# ENGR12L_Security_Alarm_v2.net
KiCad netlist of a schematic drawn in EAGLE
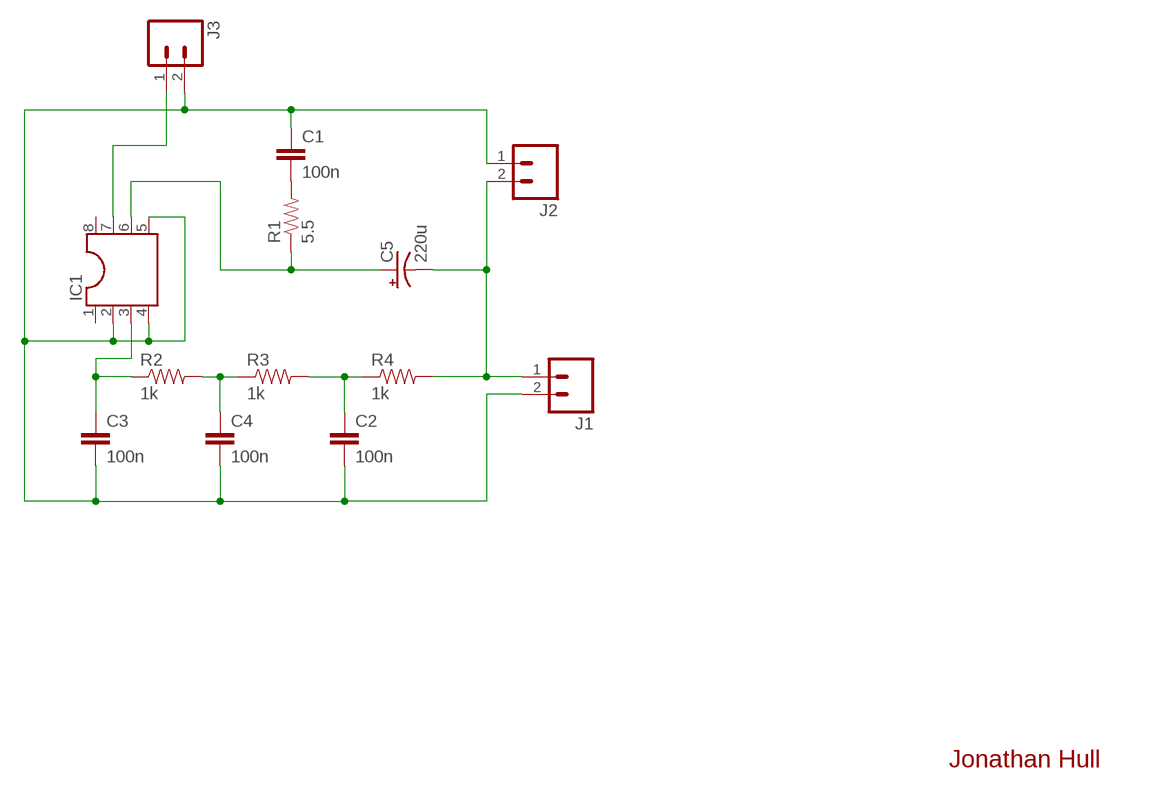
[diagram p0: schematic, sheet 1]

(export (version "E")
  (design (tool "Eeschema 10.0.6"))
  (components
    (comp (ref "C1")
      (value "100n")
      (footprint "eagle-import:CAP-PTH-SMALL")
      (libsource (lib "eagle-import") (part "CAPPTH"))
    )
    (comp (ref "C2")
      (value "100n")
      (footprint "eagle-import:CAP-PTH-SMALL")
      (libsource (lib "eagle-import") (part "CAPPTH"))
    )
    (comp (ref "C3")
      (value "100n")
      (footprint "eagle-import:CAP-PTH-SMALL")
      (libsource (lib "eagle-import") (part "CAPPTH"))
    )
    (comp (ref "C4")
      (value "100n")
      (footprint "eagle-import:CAP-PTH-SMALL")
      (libsource (lib "eagle-import") (part "CAPPTH"))
    )
    (comp (ref "C5")
      (value "220u")
      (footprint "eagle-import:CPOL-RADIAL-10UF-25V")
      (libsource (lib "eagle-import") (part "CAP_POLPTH2"))
    )
    (comp (ref "IC1")
      (value "DIL8S")
      (footprint "eagle-import:SOCKET-08")
      (libsource (lib "eagle-import") (part "DIL8S"))
    )
    (comp (ref "J1")
      (value "M023.5MM")
      (footprint "eagle-import:SCREWTERMINAL-3.5MM-2")
      (libsource (lib "eagle-import") (part "M023.5MM"))
    )
    (comp (ref "J2")
      (value "M023.5MM")
      (footprint "eagle-import:SCREWTERMINAL-3.5MM-2")
      (libsource (lib "eagle-import") (part "M023.5MM"))
    )
    (comp (ref "J3")
      (value "M023.5MM")
      (footprint "eagle-import:SCREWTERMINAL-3.5MM-2")
      (libsource (lib "eagle-import") (part "M023.5MM"))
    )
    (comp (ref "R1")
      (value "5.5")
      (footprint "eagle-import:AXIAL-0.4")
      (libsource (lib "eagle-import") (part "RESISTORPTH-1/4W"))
    )
    (comp (ref "R2")
      (value "1k")
      (footprint "eagle-import:AXIAL-0.4")
      (libsource (lib "eagle-import") (part "RESISTORPTH-1/4W"))
    )
    (comp (ref "R3")
      (value "1k")
      (footprint "eagle-import:AXIAL-0.4")
      (libsource (lib "eagle-import") (part "RESISTORPTH-1/4W"))
    )
    (comp (ref "R4")
      (value "1k")
      (footprint "eagle-import:AXIAL-0.4")
      (libsource (lib "eagle-import") (part "RESISTORPTH-1/4W"))
    )
  )
  (nets
    (net (code "1") (name "Net-(C1-Pad1)") (class "Default")
      (node (ref "C1") (pin "1") (pinfunction "1_1") (pintype "passive"))
      (node (ref "C2") (pin "2") (pinfunction "2_2") (pintype "passive"))
      (node (ref "C3") (pin "2") (pinfunction "2_2") (pintype "passive"))
      (node (ref "C4") (pin "2") (pinfunction "2_2") (pintype "passive"))
      (node (ref "IC1") (pin "2") (pinfunction "2_2") (pintype "passive"))
      (node (ref "IC1") (pin "4") (pinfunction "4_4") (pintype "passive"))
      (node (ref "IC1") (pin "5") (pinfunction "5_5") (pintype "passive"))
      (node (ref "J1") (pin "2") (pinfunction "2_2") (pintype "passive"))
      (node (ref "J2") (pin "1") (pinfunction "1_1") (pintype "passive"))
      (node (ref "J3") (pin "2") (pinfunction "2_2") (pintype "passive"))
    )
    (net (code "2") (name "Net-(C5-+)") (class "Default")
      (node (ref "C5") (pin "1") (pinfunction "+_1") (pintype "passive"))
      (node (ref "IC1") (pin "6") (pinfunction "6_6") (pintype "passive"))
      (node (ref "R1") (pin "P$1") (pinfunction "1_P$1") (pintype "passive"))
    )
    (net (code "3") (name "Net-(C5--)") (class "Default")
      (node (ref "C5") (pin "2") (pinfunction "-_2") (pintype "passive"))
      (node (ref "J1") (pin "1") (pinfunction "1_1") (pintype "passive"))
      (node (ref "J2") (pin "2") (pinfunction "2_2") (pintype "passive"))
      (node (ref "R4") (pin "P$2") (pinfunction "2_P$2") (pintype "passive"))
    )
    (net (code "4") (name "Net-(IC1-Pad7)") (class "Default")
      (node (ref "IC1") (pin "7") (pinfunction "7_7") (pintype "passive"))
      (node (ref "J3") (pin "1") (pinfunction "1_1") (pintype "passive"))
    )
    (net (code "5") (name "Net-(R1-2)") (class "Default")
      (node (ref "C1") (pin "2") (pinfunction "2_2") (pintype "passive"))
      (node (ref "R1") (pin "P$2") (pinfunction "2_P$2") (pintype "passive"))
    )
    (net (code "6") (name "Net-(R2-1)") (class "Default")
      (node (ref "C3") (pin "1") (pinfunction "1_1") (pintype "passive"))
      (node (ref "IC1") (pin "3") (pinfunction "3_3") (pintype "passive"))
      (node (ref "R2") (pin "P$1") (pinfunction "1_P$1") (pintype "passive"))
    )
    (net (code "7") (name "Net-(R2-2)") (class "Default")
      (node (ref "C4") (pin "1") (pinfunction "1_1") (pintype "passive"))
      (node (ref "R2") (pin "P$2") (pinfunction "2_P$2") (pintype "passive"))
      (node (ref "R3") (pin "P$1") (pinfunction "1_P$1") (pintype "passive"))
    )
    (net (code "8") (name "Net-(R3-2)") (class "Default")
      (node (ref "C2") (pin "1") (pinfunction "1_1") (pintype "passive"))
      (node (ref "R3") (pin "P$2") (pinfunction "2_P$2") (pintype "passive"))
      (node (ref "R4") (pin "P$1") (pinfunction "1_P$1") (pintype "passive"))
    )
    (net (code "9") (name "unconnected-(IC1-Pad1)") (class "Default")
      (node (ref "IC1") (pin "1") (pinfunction "1_1") (pintype "passive"))
    )
    (net (code "10") (name "unconnected-(IC1-Pad8)") (class "Default")
      (node (ref "IC1") (pin "8") (pinfunction "8_8") (pintype "passive"))
    )
  )
)
